# Main.net
KiCad netlist of a schematic drawn in Altium Designer
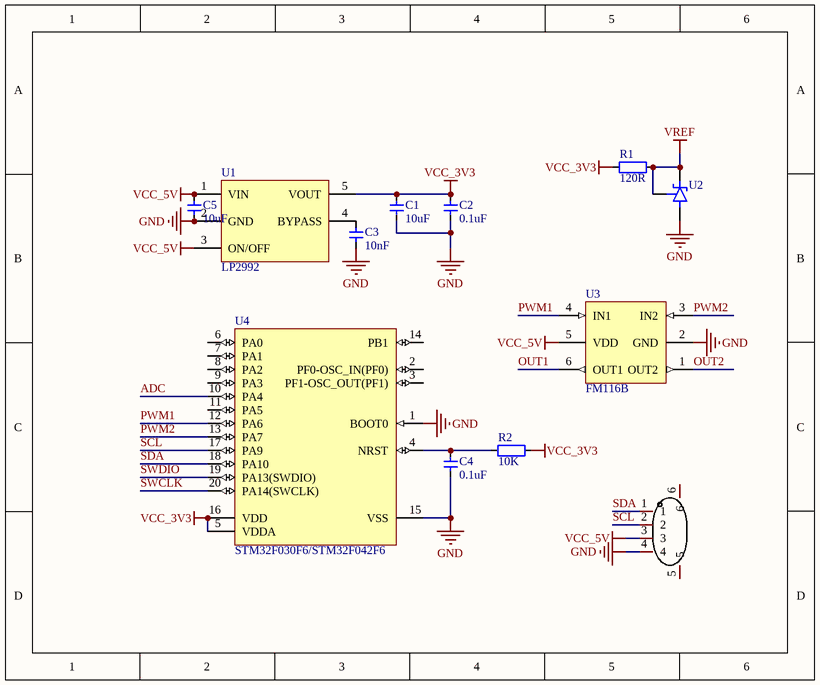
[diagram p0: Main.SchDoc]

(export (version "E")
  (design (tool "Eeschema 10.0.6"))
  (components
    (comp (ref "C1")
      (value "10uF")
      (footprint "CAP_0402")
      (description "Capacitor")
      (libsource (lib "MyPcbLib") (part "电容-0402"))
    )
    (comp (ref "C2")
      (value "0.1uF")
      (footprint "CAP_0402")
      (description "Capacitor")
      (libsource (lib "MyPcbLib") (part "电容-0402"))
    )
    (comp (ref "C3")
      (value "10nF")
      (footprint "CAP_0402")
      (description "Capacitor")
      (libsource (lib "MyPcbLib") (part "电容-0402"))
    )
    (comp (ref "C4")
      (value "0.1uF")
      (footprint "CAP_0402")
      (description "Capacitor")
      (libsource (lib "MyPcbLib") (part "电容-0402"))
    )
    (comp (ref "C5")
      (value "10uF")
      (footprint "CAP_0402")
      (description "Capacitor")
      (libsource (lib "MyPcbLib") (part "电容-0402"))
    )
    (comp (ref "FPC1")
      (value "0.5K-DX-4PWB")
      (footprint "FPC-SMD_4P-P0.50_DEALON_0.5K-DX-4PWB")
      (fields (field (name "MANUFACTURER") "HDGC(华德共创)"))
      (libsource (lib "altium-import") (part "root_0_0.5K-DX-4PWB_"))
    )
    (comp (ref "R1")
      (value "120R")
      (footprint "RES_0402")
      (description "Resistor")
      (libsource (lib "") (part "电阻-0402_1"))
    )
    (comp (ref "R2")
      (value "10K")
      (footprint "RES_0402")
      (description "Resistor")
      (libsource (lib "MyPcbLib") (part "电阻-0402"))
    )
    (comp (ref "U1")
      (value "LP2992")
      (footprint "SOT23-5")
      (description "LDO")
      (libsource (lib "MyPcbLib") (part "LP2992"))
    )
    (comp (ref "U2")
      (value "TL431IDBZT")
      (footprint "SOT23-3")
      (description "Adjustable precision shunt regulator 3-SOT-23 -40 to 85")
      (fields (field (name "MF") "Texas Instruments"))
      (libsource (lib "MyPcbLib") (part "TL431IDBZT"))
    )
    (comp (ref "U3")
      (value "FM116B")
      (footprint "SOT23-6")
      (fields (field (name "PARTNUMBER") "24LC256-I/ST"))
      (libsource (lib "MyPcbLib") (part "FM116B"))
    )
    (comp (ref "U4")
      (value "STM32F030F6/STM32F042F6")
      (footprint "TSSOP-20")
      (fields (field (name "PARTNUMBER") "STM32F030F4P6"))
      (libsource (lib "MyPcbLib") (part "STM32F030F4P6"))
    )
  )
  (nets
    (net (code "1") (name "/ADC") (class "Default")
      (node (ref "U4") (pin "10") (pinfunction "PA4_10") (pintype "bidirectional"))
    )
    (net (code "2") (name "/OUT1") (class "Default")
      (node (ref "U3") (pin "6") (pinfunction "OUT1_6") (pintype "output"))
    )
    (net (code "3") (name "/OUT2") (class "Default")
      (node (ref "U3") (pin "1") (pinfunction "OUT2_1") (pintype "output"))
    )
    (net (code "4") (name "/PWM1") (class "Default")
      (node (ref "U3") (pin "4") (pinfunction "IN1_4") (pintype "input"))
      (node (ref "U4") (pin "12") (pinfunction "PA6_12") (pintype "bidirectional"))
    )
    (net (code "5") (name "/PWM2") (class "Default")
      (node (ref "U3") (pin "3") (pinfunction "IN2_3") (pintype "input"))
      (node (ref "U4") (pin "13") (pinfunction "PA7_13") (pintype "bidirectional"))
    )
    (net (code "6") (name "/SCL") (class "Default")
      (node (ref "FPC1") (pin "2") (pinfunction "2_2") (pintype "passive"))
      (node (ref "U4") (pin "17") (pinfunction "PA9_17") (pintype "bidirectional"))
    )
    (net (code "7") (name "/SDA") (class "Default")
      (node (ref "FPC1") (pin "1") (pinfunction "1_1") (pintype "passive"))
      (node (ref "U4") (pin "18") (pinfunction "PA10_18") (pintype "bidirectional"))
    )
    (net (code "8") (name "/SWCLK") (class "Default")
      (node (ref "U4") (pin "20") (pinfunction "PA14(SWCLK)_20") (pintype "bidirectional"))
    )
    (net (code "9") (name "/SWDIO") (class "Default")
      (node (ref "U4") (pin "19") (pinfunction "PA13(SWDIO)_19") (pintype "bidirectional"))
    )
    (net (code "10") (name "GND") (class "Default")
      (node (ref "C1") (pin "1") (pinfunction "1_1") (pintype "passive"))
      (node (ref "C2") (pin "1") (pinfunction "1_1") (pintype "passive"))
      (node (ref "C3") (pin "2") (pinfunction "2_2") (pintype "passive"))
      (node (ref "C4") (pin "1") (pinfunction "1_1") (pintype "passive"))
      (node (ref "C5") (pin "1") (pinfunction "1_1") (pintype "passive"))
      (node (ref "FPC1") (pin "4") (pinfunction "4_4") (pintype "passive"))
      (node (ref "U1") (pin "2") (pinfunction "GND_2") (pintype "passive"))
      (node (ref "U2") (pin "3") (pinfunction "ANODE_3") (pintype "passive"))
      (node (ref "U3") (pin "2") (pinfunction "GND_2") (pintype "power_in"))
      (node (ref "U4") (pin "1") (pinfunction "BOOT0_1") (pintype "input"))
      (node (ref "U4") (pin "15") (pinfunction "VSS_15") (pintype "power_in"))
    )
    (net (code "11") (name "Net-(U1-BYPASS)") (class "Default")
      (node (ref "C3") (pin "1") (pinfunction "1_1") (pintype "passive"))
      (node (ref "U1") (pin "4") (pinfunction "BYPASS_4") (pintype "passive"))
    )
    (net (code "12") (name "Net-(U4-NRST)") (class "Default")
      (node (ref "C4") (pin "2") (pinfunction "2_2") (pintype "passive"))
      (node (ref "R2") (pin "2") (pinfunction "2_2") (pintype "passive"))
      (node (ref "U4") (pin "4") (pinfunction "NRST_4") (pintype "bidirectional"))
    )
    (net (code "13") (name "VCC_3V3") (class "Default")
      (node (ref "C1") (pin "2") (pinfunction "2_2") (pintype "passive"))
      (node (ref "C2") (pin "2") (pinfunction "2_2") (pintype "passive"))
      (node (ref "R1") (pin "1") (pinfunction "1_1") (pintype "passive"))
      (node (ref "R2") (pin "1") (pinfunction "1_1") (pintype "passive"))
      (node (ref "U1") (pin "5") (pinfunction "VOUT_5") (pintype "passive"))
      (node (ref "U4") (pin "16") (pinfunction "VDD_16") (pintype "power_in"))
      (node (ref "U4") (pin "5") (pinfunction "VDDA_5") (pintype "power_in"))
    )
    (net (code "14") (name "VCC_5V") (class "Default")
      (node (ref "C5") (pin "2") (pinfunction "2_2") (pintype "passive"))
      (node (ref "FPC1") (pin "3") (pinfunction "3_3") (pintype "passive"))
      (node (ref "U1") (pin "1") (pinfunction "VIN_1") (pintype "passive"))
      (node (ref "U1") (pin "3") (pinfunction "ON/OFF_3") (pintype "passive"))
      (node (ref "U3") (pin "5") (pinfunction "VDD_5") (pintype "power_in"))
    )
    (net (code "15") (name "VREF") (class "Default")
      (node (ref "R1") (pin "2") (pinfunction "2_2") (pintype "passive"))
      (node (ref "U2") (pin "1") (pinfunction "CATHODE_1") (pintype "passive"))
      (node (ref "U2") (pin "2") (pinfunction "REF_2") (pintype "passive"))
    )
    (net (code "16") (name "unconnected-(FPC1-Pad5)") (class "Default")
      (node (ref "FPC1") (pin "5") (pinfunction "5_5") (pintype "passive"))
    )
    (net (code "17") (name "unconnected-(FPC1-Pad6)") (class "Default")
      (node (ref "FPC1") (pin "6") (pinfunction "6_6") (pintype "passive"))
    )
    (net (code "18") (name "unconnected-(U4-PA0-Pad6)") (class "Default")
      (node (ref "U4") (pin "6") (pinfunction "PA0_6") (pintype "bidirectional"))
    )
    (net (code "19") (name "unconnected-(U4-PA1-Pad7)") (class "Default")
      (node (ref "U4") (pin "7") (pinfunction "PA1_7") (pintype "bidirectional"))
    )
    (net (code "20") (name "unconnected-(U4-PA2-Pad8)") (class "Default")
      (node (ref "U4") (pin "8") (pinfunction "PA2_8") (pintype "bidirectional"))
    )
    (net (code "21") (name "unconnected-(U4-PA3-Pad9)") (class "Default")
      (node (ref "U4") (pin "9") (pinfunction "PA3_9") (pintype "bidirectional"))
    )
    (net (code "22") (name "unconnected-(U4-PA5-Pad11)") (class "Default")
      (node (ref "U4") (pin "11") (pinfunction "PA5_11") (pintype "bidirectional"))
    )
    (net (code "23") (name "unconnected-(U4-PB1-Pad14)") (class "Default")
      (node (ref "U4") (pin "14") (pinfunction "PB1_14") (pintype "bidirectional"))
    )
    (net (code "24") (name "unconnected-(U4-PF0-OSC_IN(PF0)-Pad2)") (class "Default")
      (node (ref "U4") (pin "2") (pinfunction "PF0-OSC_IN(PF0)_2") (pintype "bidirectional"))
    )
    (net (code "25") (name "unconnected-(U4-PF1-OSC_OUT(PF1)-Pad3)") (class "Default")
      (node (ref "U4") (pin "3") (pinfunction "PF1-OSC_OUT(PF1)_3") (pintype "bidirectional"))
    )
  )
)
